# ethernet_adapter_stepper.net
KiCad netlist of a schematic drawn in EAGLE
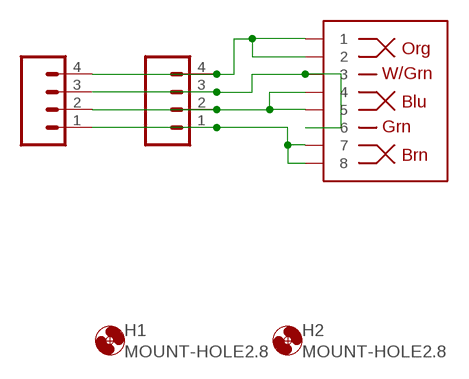
[diagram p0: schematic, sheet 1]

(export (version "E")
  (design (tool "Eeschema 10.0.6"))
  (components
    (comp (ref "H1")
      (value "MOUNT-HOLE2.8")
      (footprint "eagle-import:2,8")
      (libsource (lib "eagle-import") (part "MOUNT-HOLE2.8"))
    )
    (comp (ref "H2")
      (value "MOUNT-HOLE2.8")
      (footprint "eagle-import:2,8")
      (libsource (lib "eagle-import") (part "MOUNT-HOLE2.8"))
    )
    (comp (ref "J1")
      (value "RJ45")
      (footprint "eagle-import:RJ45-8")
      (libsource (lib "eagle-import") (part "RJ45-8"))
    )
    (comp (ref "J2")
      (value "CONN_04")
      (footprint "eagle-import:1X04")
      (libsource (lib "eagle-import") (part "CONN_04"))
    )
    (comp (ref "J4")
      (value "CONN_04SCREW")
      (footprint "eagle-import:SCREWTERMINAL-3.5MM-4")
      (libsource (lib "eagle-import") (part "CONN_04SCREW"))
    )
  )
  (nets
    (net (code "1") (name "Net-(J1-Pad1)") (class "Default")
      (node (ref "J1") (pin "1") (pinfunction "1_1") (pintype "bidirectional"))
      (node (ref "J1") (pin "2") (pinfunction "2_2") (pintype "bidirectional"))
      (node (ref "J2") (pin "4") (pinfunction "4_4") (pintype "passive"))
      (node (ref "J4") (pin "4") (pinfunction "4_4") (pintype "passive"))
    )
    (net (code "2") (name "Net-(J1-Pad3)") (class "Default")
      (node (ref "J1") (pin "3") (pinfunction "3_3") (pintype "bidirectional"))
      (node (ref "J1") (pin "6") (pinfunction "6_6") (pintype "bidirectional"))
      (node (ref "J2") (pin "3") (pinfunction "3_3") (pintype "passive"))
      (node (ref "J4") (pin "3") (pinfunction "3_3") (pintype "passive"))
    )
    (net (code "3") (name "Net-(J1-Pad4)") (class "Default")
      (node (ref "J1") (pin "4") (pinfunction "4_4") (pintype "bidirectional"))
      (node (ref "J1") (pin "5") (pinfunction "5_5") (pintype "bidirectional"))
      (node (ref "J2") (pin "2") (pinfunction "2_2") (pintype "passive"))
      (node (ref "J4") (pin "2") (pinfunction "2_2") (pintype "passive"))
    )
    (net (code "4") (name "Net-(J1-Pad7)") (class "Default")
      (node (ref "J1") (pin "7") (pinfunction "7_7") (pintype "bidirectional"))
      (node (ref "J1") (pin "8") (pinfunction "8_8") (pintype "bidirectional"))
      (node (ref "J2") (pin "1") (pinfunction "1_1") (pintype "passive"))
      (node (ref "J4") (pin "1") (pinfunction "1_1") (pintype "passive"))
    )
  )
)
